# lesion-breakout.net
KiCad netlist of a schematic drawn in EAGLE
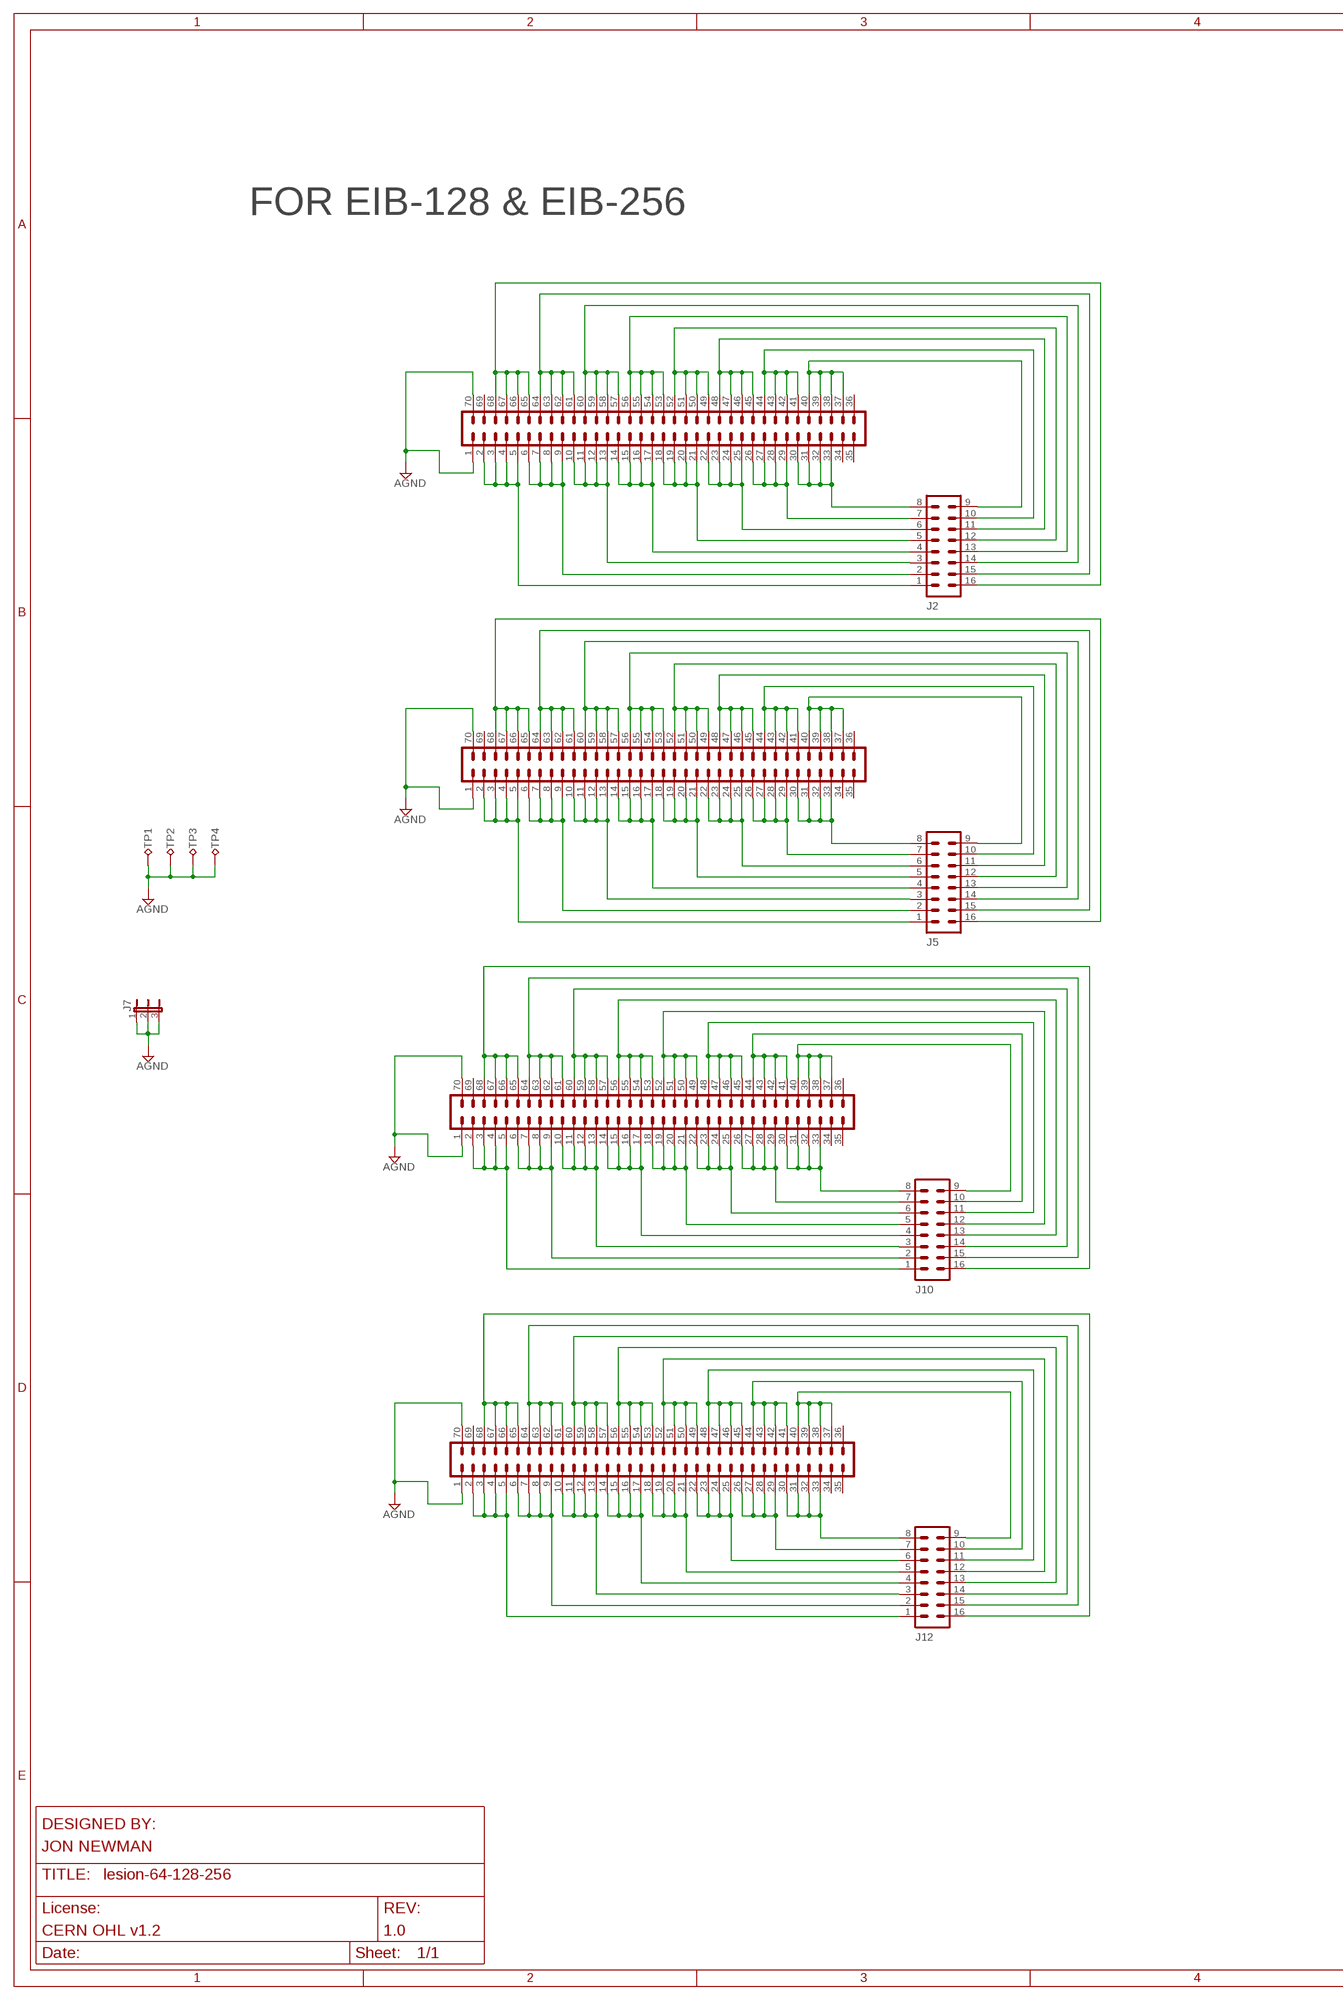
[diagram p0: schematic, sheet 1, part 1 of 3]
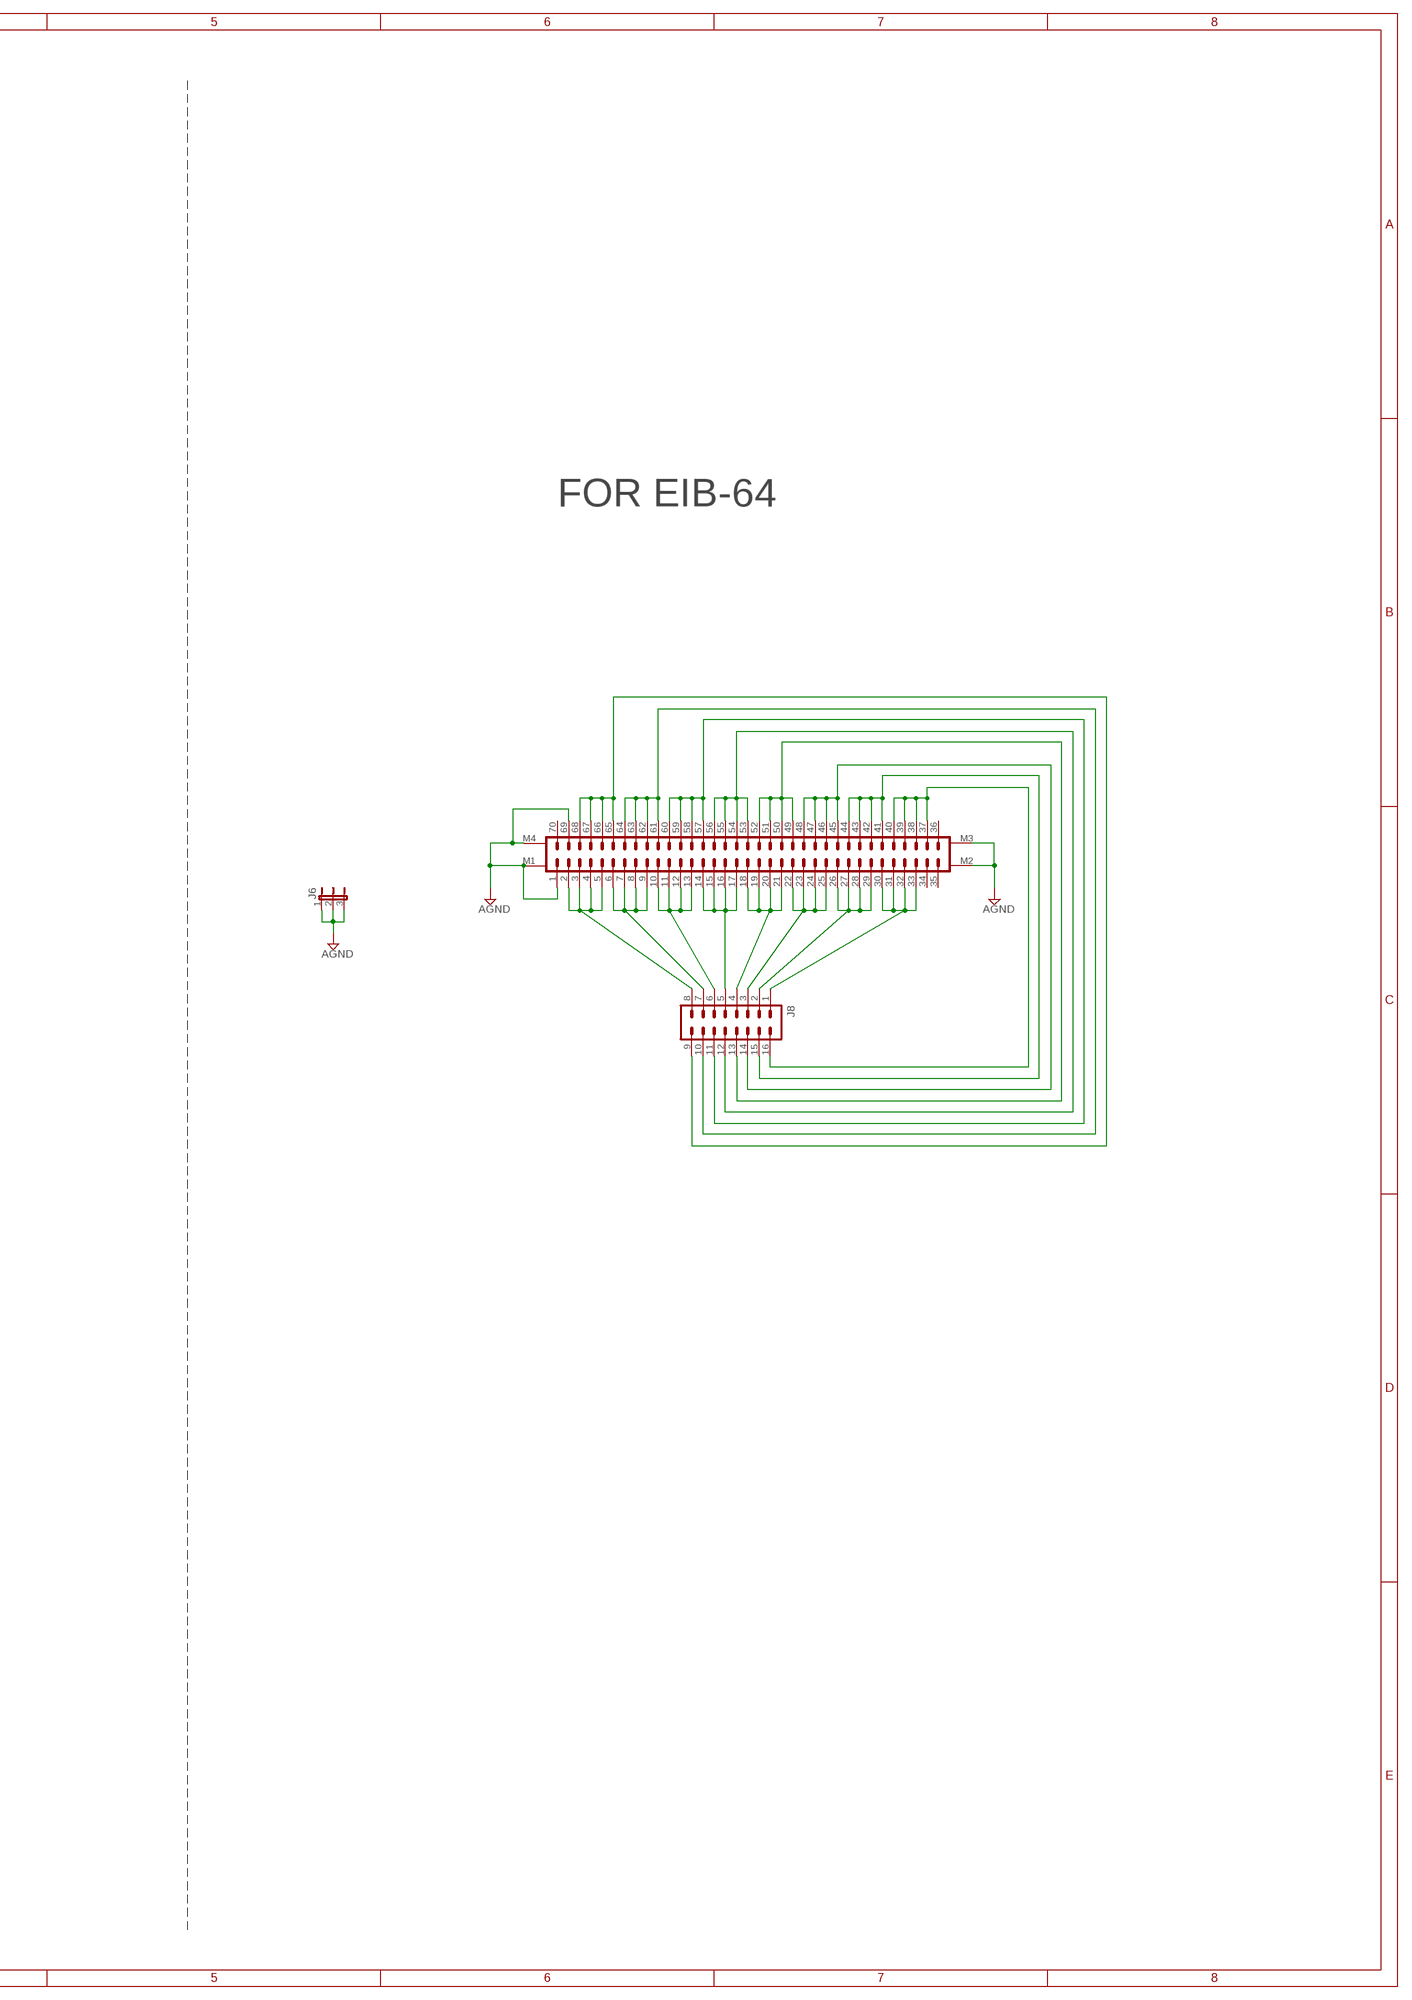
[diagram p1: schematic, sheet 1, part 2 of 3]
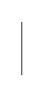
[diagram p2: schematic, sheet 1, part 3 of 3]

(export (version "E")
  (design (tool "Eeschema 10.0.6"))
  (components
    (comp (ref "J1")
      (value "DF40C(2.0)-70DS-0.4V(51)")
      (footprint "eagle-import:DF40-70REC")
      (libsource (lib "eagle-import") (part "PINHD-2X35_DF40REC"))
    )
    (comp (ref "J2")
      (value "PINHD-2X8_SMD_0.5\"")
      (footprint "eagle-import:JP2X8_SMD_0.5_")
      (libsource (lib "eagle-import") (part "PINHD-2X8_SMD_0.5{dblquote}"))
    )
    (comp (ref "J3")
      (value "DF40C(2.0)-70DS-0.4V(51)")
      (footprint "eagle-import:DF40-70REC")
      (libsource (lib "eagle-import") (part "PINHD-2X35_DF40REC"))
    )
    (comp (ref "J4")
      (value "DF40C-70DP-0.4V(51)")
      (footprint "eagle-import:DF40-70HEAD-LESS-SILK")
      (libsource (lib "eagle-import") (part "PINHD-2X35+4DF40-70HEAD-LESS-SILK"))
    )
    (comp (ref "J5")
      (value "PINHD-2X8_SMD_0.5\"")
      (footprint "eagle-import:JP2X8_SMD_0.5_")
      (libsource (lib "eagle-import") (part "PINHD-2X8_SMD_0.5{dblquote}"))
    )
    (comp (ref "J6")
      (value "JP3E_SMD-0.05")
      (footprint "eagle-import:JP3_SMD-0.05")
      (libsource (lib "eagle-import") (part "JP3E_SMD-0.05"))
    )
    (comp (ref "J7")
      (value "JP3E_SMD-0.05")
      (footprint "eagle-import:JP3_SMD-0.05")
      (libsource (lib "eagle-import") (part "JP3E_SMD-0.05"))
    )
    (comp (ref "J8")
      (value "PINHD-2X8_SMD_0.5\"")
      (footprint "eagle-import:JP2X8_SMD_0.5_")
      (libsource (lib "eagle-import") (part "PINHD-2X8_SMD_0.5{dblquote}"))
    )
    (comp (ref "J9")
      (value "DF40C(2.0)-70DS-0.4V(51)")
      (footprint "eagle-import:DF40-70REC")
      (libsource (lib "eagle-import") (part "PINHD-2X35_DF40REC"))
    )
    (comp (ref "J10")
      (value "PINHD-2X8_SMD_0.5\"")
      (footprint "eagle-import:JP2X8_SMD_0.5_")
      (libsource (lib "eagle-import") (part "PINHD-2X8_SMD_0.5{dblquote}"))
    )
    (comp (ref "J11")
      (value "DF40C(2.0)-70DS-0.4V(51)")
      (footprint "eagle-import:DF40-70REC")
      (libsource (lib "eagle-import") (part "PINHD-2X35_DF40REC"))
    )
    (comp (ref "J12")
      (value "PINHD-2X8_SMD_0.5\"")
      (footprint "eagle-import:JP2X8_SMD_0.5_")
      (libsource (lib "eagle-import") (part "PINHD-2X8_SMD_0.5{dblquote}"))
    )
    (comp (ref "TP1")
      (value "TP_1MM")
      (footprint "eagle-import:TESTPOINT_1MM")
      (libsource (lib "eagle-import") (part "TP_1MM"))
    )
    (comp (ref "TP2")
      (value "TP_1MM")
      (footprint "eagle-import:TESTPOINT_1MM")
      (libsource (lib "eagle-import") (part "TP_1MM"))
    )
    (comp (ref "TP3")
      (value "TP_1MM")
      (footprint "eagle-import:TESTPOINT_1MM")
      (libsource (lib "eagle-import") (part "TP_1MM"))
    )
    (comp (ref "TP4")
      (value "TP_1MM")
      (footprint "eagle-import:TESTPOINT_1MM")
      (libsource (lib "eagle-import") (part "TP_1MM"))
    )
  )
  (nets
    (net (code "1") (name "AGND") (class "Default")
      (node (ref "J1") (pin "1") (pinfunction "1_1") (pintype "bidirectional"))
      (node (ref "J1") (pin "70") (pinfunction "70_70") (pintype "bidirectional"))
      (node (ref "J11") (pin "1") (pinfunction "1_1") (pintype "bidirectional"))
      (node (ref "J11") (pin "70") (pinfunction "70_70") (pintype "bidirectional"))
      (node (ref "J3") (pin "1") (pinfunction "1_1") (pintype "bidirectional"))
      (node (ref "J3") (pin "70") (pinfunction "70_70") (pintype "bidirectional"))
      (node (ref "J4") (pin "1") (pinfunction "1_1") (pintype "bidirectional"))
      (node (ref "J4") (pin "69") (pinfunction "69_69") (pintype "bidirectional"))
      (node (ref "J4") (pin "M1") (pinfunction "M1_M1") (pintype "bidirectional"))
      (node (ref "J4") (pin "M2") (pinfunction "M2_M2") (pintype "bidirectional"))
      (node (ref "J4") (pin "M3") (pinfunction "M3_M3") (pintype "bidirectional"))
      (node (ref "J4") (pin "M4") (pinfunction "M4_M4") (pintype "bidirectional"))
      (node (ref "J6") (pin "1") (pinfunction "1_1") (pintype "passive"))
      (node (ref "J6") (pin "2") (pinfunction "2_2") (pintype "passive"))
      (node (ref "J6") (pin "3") (pinfunction "3_3") (pintype "passive"))
      (node (ref "J7") (pin "1") (pinfunction "1_1") (pintype "passive"))
      (node (ref "J7") (pin "2") (pinfunction "2_2") (pintype "passive"))
      (node (ref "J7") (pin "3") (pinfunction "3_3") (pintype "passive"))
      (node (ref "J9") (pin "1") (pinfunction "1_1") (pintype "bidirectional"))
      (node (ref "J9") (pin "70") (pinfunction "70_70") (pintype "bidirectional"))
      (node (ref "TP1") (pin "1") (pinfunction "TP_1") (pintype "bidirectional"))
      (node (ref "TP2") (pin "1") (pinfunction "TP_1") (pintype "bidirectional"))
      (node (ref "TP3") (pin "1") (pinfunction "TP_1") (pintype "bidirectional"))
      (node (ref "TP4") (pin "1") (pinfunction "TP_1") (pintype "bidirectional"))
    )
    (net (code "2") (name "Net-(J1-Pad2)") (class "Default")
      (node (ref "J1") (pin "2") (pinfunction "2_2") (pintype "bidirectional"))
      (node (ref "J1") (pin "3") (pinfunction "3_3") (pintype "bidirectional"))
      (node (ref "J1") (pin "4") (pinfunction "4_4") (pintype "bidirectional"))
      (node (ref "J1") (pin "5") (pinfunction "5_5") (pintype "bidirectional"))
      (node (ref "J2") (pin "1") (pinfunction "1_1") (pintype "passive"))
    )
    (net (code "3") (name "Net-(J2-2)") (class "Default")
      (node (ref "J1") (pin "65") (pinfunction "65_65") (pintype "bidirectional"))
      (node (ref "J1") (pin "66") (pinfunction "66_66") (pintype "bidirectional"))
      (node (ref "J1") (pin "67") (pinfunction "67_67") (pintype "bidirectional"))
      (node (ref "J1") (pin "68") (pinfunction "68_68") (pintype "bidirectional"))
      (node (ref "J2") (pin "16") (pinfunction "2_16") (pintype "passive"))
    )
    (net (code "4") (name "Net-(J2-3)") (class "Default")
      (node (ref "J1") (pin "6") (pinfunction "6_6") (pintype "bidirectional"))
      (node (ref "J1") (pin "7") (pinfunction "7_7") (pintype "bidirectional"))
      (node (ref "J1") (pin "8") (pinfunction "8_8") (pintype "bidirectional"))
      (node (ref "J1") (pin "9") (pinfunction "9_9") (pintype "bidirectional"))
      (node (ref "J2") (pin "2") (pinfunction "3_2") (pintype "passive"))
    )
    (net (code "5") (name "Net-(J2-4)") (class "Default")
      (node (ref "J1") (pin "61") (pinfunction "61_61") (pintype "bidirectional"))
      (node (ref "J1") (pin "62") (pinfunction "62_62") (pintype "bidirectional"))
      (node (ref "J1") (pin "63") (pinfunction "63_63") (pintype "bidirectional"))
      (node (ref "J1") (pin "64") (pinfunction "64_64") (pintype "bidirectional"))
      (node (ref "J2") (pin "15") (pinfunction "4_15") (pintype "passive"))
    )
    (net (code "6") (name "Net-(J2-5)") (class "Default")
      (node (ref "J1") (pin "10") (pinfunction "10_10") (pintype "bidirectional"))
      (node (ref "J1") (pin "11") (pinfunction "11_11") (pintype "bidirectional"))
      (node (ref "J1") (pin "12") (pinfunction "12_12") (pintype "bidirectional"))
      (node (ref "J1") (pin "13") (pinfunction "13_13") (pintype "bidirectional"))
      (node (ref "J2") (pin "3") (pinfunction "5_3") (pintype "passive"))
    )
    (net (code "7") (name "Net-(J2-6)") (class "Default")
      (node (ref "J1") (pin "57") (pinfunction "57_57") (pintype "bidirectional"))
      (node (ref "J1") (pin "58") (pinfunction "58_58") (pintype "bidirectional"))
      (node (ref "J1") (pin "59") (pinfunction "59_59") (pintype "bidirectional"))
      (node (ref "J1") (pin "60") (pinfunction "60_60") (pintype "bidirectional"))
      (node (ref "J2") (pin "14") (pinfunction "6_14") (pintype "passive"))
    )
    (net (code "8") (name "Net-(J2-7)") (class "Default")
      (node (ref "J1") (pin "14") (pinfunction "14_14") (pintype "bidirectional"))
      (node (ref "J1") (pin "15") (pinfunction "15_15") (pintype "bidirectional"))
      (node (ref "J1") (pin "16") (pinfunction "16_16") (pintype "bidirectional"))
      (node (ref "J1") (pin "17") (pinfunction "17_17") (pintype "bidirectional"))
      (node (ref "J2") (pin "4") (pinfunction "7_4") (pintype "passive"))
    )
    (net (code "9") (name "Net-(J2-8)") (class "Default")
      (node (ref "J1") (pin "53") (pinfunction "53_53") (pintype "bidirectional"))
      (node (ref "J1") (pin "54") (pinfunction "54_54") (pintype "bidirectional"))
      (node (ref "J1") (pin "55") (pinfunction "55_55") (pintype "bidirectional"))
      (node (ref "J1") (pin "56") (pinfunction "56_56") (pintype "bidirectional"))
      (node (ref "J2") (pin "13") (pinfunction "8_13") (pintype "passive"))
    )
    (net (code "10") (name "Net-(J2-9)") (class "Default")
      (node (ref "J1") (pin "18") (pinfunction "18_18") (pintype "bidirectional"))
      (node (ref "J1") (pin "19") (pinfunction "19_19") (pintype "bidirectional"))
      (node (ref "J1") (pin "20") (pinfunction "20_20") (pintype "bidirectional"))
      (node (ref "J1") (pin "21") (pinfunction "21_21") (pintype "bidirectional"))
      (node (ref "J2") (pin "5") (pinfunction "9_5") (pintype "passive"))
    )
    (net (code "11") (name "Net-(J2-10)") (class "Default")
      (node (ref "J1") (pin "49") (pinfunction "49_49") (pintype "bidirectional"))
      (node (ref "J1") (pin "50") (pinfunction "50_50") (pintype "bidirectional"))
      (node (ref "J1") (pin "51") (pinfunction "51_51") (pintype "bidirectional"))
      (node (ref "J1") (pin "52") (pinfunction "52_52") (pintype "bidirectional"))
      (node (ref "J2") (pin "12") (pinfunction "10_12") (pintype "passive"))
    )
    (net (code "12") (name "Net-(J2-11)") (class "Default")
      (node (ref "J1") (pin "22") (pinfunction "22_22") (pintype "bidirectional"))
      (node (ref "J1") (pin "23") (pinfunction "23_23") (pintype "bidirectional"))
      (node (ref "J1") (pin "24") (pinfunction "24_24") (pintype "bidirectional"))
      (node (ref "J1") (pin "25") (pinfunction "25_25") (pintype "bidirectional"))
      (node (ref "J2") (pin "6") (pinfunction "11_6") (pintype "passive"))
    )
    (net (code "13") (name "Net-(J2-12)") (class "Default")
      (node (ref "J1") (pin "45") (pinfunction "45_45") (pintype "bidirectional"))
      (node (ref "J1") (pin "46") (pinfunction "46_46") (pintype "bidirectional"))
      (node (ref "J1") (pin "47") (pinfunction "47_47") (pintype "bidirectional"))
      (node (ref "J1") (pin "48") (pinfunction "48_48") (pintype "bidirectional"))
      (node (ref "J2") (pin "11") (pinfunction "12_11") (pintype "passive"))
    )
    (net (code "14") (name "Net-(J2-13)") (class "Default")
      (node (ref "J1") (pin "26") (pinfunction "26_26") (pintype "bidirectional"))
      (node (ref "J1") (pin "27") (pinfunction "27_27") (pintype "bidirectional"))
      (node (ref "J1") (pin "28") (pinfunction "28_28") (pintype "bidirectional"))
      (node (ref "J1") (pin "29") (pinfunction "29_29") (pintype "bidirectional"))
      (node (ref "J2") (pin "7") (pinfunction "13_7") (pintype "passive"))
    )
    (net (code "15") (name "Net-(J2-14)") (class "Default")
      (node (ref "J1") (pin "41") (pinfunction "41_41") (pintype "bidirectional"))
      (node (ref "J1") (pin "42") (pinfunction "42_42") (pintype "bidirectional"))
      (node (ref "J1") (pin "43") (pinfunction "43_43") (pintype "bidirectional"))
      (node (ref "J1") (pin "44") (pinfunction "44_44") (pintype "bidirectional"))
      (node (ref "J2") (pin "10") (pinfunction "14_10") (pintype "passive"))
    )
    (net (code "16") (name "Net-(J2-15)") (class "Default")
      (node (ref "J1") (pin "30") (pinfunction "30_30") (pintype "bidirectional"))
      (node (ref "J1") (pin "31") (pinfunction "31_31") (pintype "bidirectional"))
      (node (ref "J1") (pin "32") (pinfunction "32_32") (pintype "bidirectional"))
      (node (ref "J1") (pin "33") (pinfunction "33_33") (pintype "bidirectional"))
      (node (ref "J2") (pin "8") (pinfunction "15_8") (pintype "passive"))
    )
    (net (code "17") (name "Net-(J2-16)") (class "Default")
      (node (ref "J1") (pin "37") (pinfunction "37_37") (pintype "bidirectional"))
      (node (ref "J1") (pin "38") (pinfunction "38_38") (pintype "bidirectional"))
      (node (ref "J1") (pin "39") (pinfunction "39_39") (pintype "bidirectional"))
      (node (ref "J1") (pin "40") (pinfunction "40_40") (pintype "bidirectional"))
      (node (ref "J2") (pin "9") (pinfunction "16_9") (pintype "passive"))
    )
    (net (code "18") (name "Net-(J3-Pad2)") (class "Default")
      (node (ref "J3") (pin "2") (pinfunction "2_2") (pintype "bidirectional"))
      (node (ref "J3") (pin "3") (pinfunction "3_3") (pintype "bidirectional"))
      (node (ref "J3") (pin "4") (pinfunction "4_4") (pintype "bidirectional"))
      (node (ref "J3") (pin "5") (pinfunction "5_5") (pintype "bidirectional"))
      (node (ref "J5") (pin "1") (pinfunction "1_1") (pintype "passive"))
    )
    (net (code "19") (name "Net-(J4-Pad30)") (class "Default")
      (node (ref "J4") (pin "30") (pinfunction "30_30") (pintype "bidirectional"))
      (node (ref "J4") (pin "31") (pinfunction "31_31") (pintype "bidirectional"))
      (node (ref "J4") (pin "32") (pinfunction "32_32") (pintype "bidirectional"))
      (node (ref "J4") (pin "33") (pinfunction "33_33") (pintype "bidirectional"))
      (node (ref "J8") (pin "1") (pinfunction "1_1") (pintype "passive"))
    )
    (net (code "20") (name "Net-(J5-2)") (class "Default")
      (node (ref "J3") (pin "65") (pinfunction "65_65") (pintype "bidirectional"))
      (node (ref "J3") (pin "66") (pinfunction "66_66") (pintype "bidirectional"))
      (node (ref "J3") (pin "67") (pinfunction "67_67") (pintype "bidirectional"))
      (node (ref "J3") (pin "68") (pinfunction "68_68") (pintype "bidirectional"))
      (node (ref "J5") (pin "16") (pinfunction "2_16") (pintype "passive"))
    )
    (net (code "21") (name "Net-(J5-3)") (class "Default")
      (node (ref "J3") (pin "6") (pinfunction "6_6") (pintype "bidirectional"))
      (node (ref "J3") (pin "7") (pinfunction "7_7") (pintype "bidirectional"))
      (node (ref "J3") (pin "8") (pinfunction "8_8") (pintype "bidirectional"))
      (node (ref "J3") (pin "9") (pinfunction "9_9") (pintype "bidirectional"))
      (node (ref "J5") (pin "2") (pinfunction "3_2") (pintype "passive"))
    )
    (net (code "22") (name "Net-(J5-4)") (class "Default")
      (node (ref "J3") (pin "61") (pinfunction "61_61") (pintype "bidirectional"))
      (node (ref "J3") (pin "62") (pinfunction "62_62") (pintype "bidirectional"))
      (node (ref "J3") (pin "63") (pinfunction "63_63") (pintype "bidirectional"))
      (node (ref "J3") (pin "64") (pinfunction "64_64") (pintype "bidirectional"))
      (node (ref "J5") (pin "15") (pinfunction "4_15") (pintype "passive"))
    )
    (net (code "23") (name "Net-(J5-5)") (class "Default")
      (node (ref "J3") (pin "10") (pinfunction "10_10") (pintype "bidirectional"))
      (node (ref "J3") (pin "11") (pinfunction "11_11") (pintype "bidirectional"))
      (node (ref "J3") (pin "12") (pinfunction "12_12") (pintype "bidirectional"))
      (node (ref "J3") (pin "13") (pinfunction "13_13") (pintype "bidirectional"))
      (node (ref "J5") (pin "3") (pinfunction "5_3") (pintype "passive"))
    )
    (net (code "24") (name "Net-(J5-6)") (class "Default")
      (node (ref "J3") (pin "57") (pinfunction "57_57") (pintype "bidirectional"))
      (node (ref "J3") (pin "58") (pinfunction "58_58") (pintype "bidirectional"))
      (node (ref "J3") (pin "59") (pinfunction "59_59") (pintype "bidirectional"))
      (node (ref "J3") (pin "60") (pinfunction "60_60") (pintype "bidirectional"))
      (node (ref "J5") (pin "14") (pinfunction "6_14") (pintype "passive"))
    )
    (net (code "25") (name "Net-(J5-7)") (class "Default")
      (node (ref "J3") (pin "14") (pinfunction "14_14") (pintype "bidirectional"))
      (node (ref "J3") (pin "15") (pinfunction "15_15") (pintype "bidirectional"))
      (node (ref "J3") (pin "16") (pinfunction "16_16") (pintype "bidirectional"))
      (node (ref "J3") (pin "17") (pinfunction "17_17") (pintype "bidirectional"))
      (node (ref "J5") (pin "4") (pinfunction "7_4") (pintype "passive"))
    )
    (net (code "26") (name "Net-(J5-8)") (class "Default")
      (node (ref "J3") (pin "53") (pinfunction "53_53") (pintype "bidirectional"))
      (node (ref "J3") (pin "54") (pinfunction "54_54") (pintype "bidirectional"))
      (node (ref "J3") (pin "55") (pinfunction "55_55") (pintype "bidirectional"))
      (node (ref "J3") (pin "56") (pinfunction "56_56") (pintype "bidirectional"))
      (node (ref "J5") (pin "13") (pinfunction "8_13") (pintype "passive"))
    )
    (net (code "27") (name "Net-(J5-9)") (class "Default")
      (node (ref "J3") (pin "18") (pinfunction "18_18") (pintype "bidirectional"))
      (node (ref "J3") (pin "19") (pinfunction "19_19") (pintype "bidirectional"))
      (node (ref "J3") (pin "20") (pinfunction "20_20") (pintype "bidirectional"))
      (node (ref "J3") (pin "21") (pinfunction "21_21") (pintype "bidirectional"))
      (node (ref "J5") (pin "5") (pinfunction "9_5") (pintype "passive"))
    )
    (net (code "28") (name "Net-(J5-10)") (class "Default")
      (node (ref "J3") (pin "49") (pinfunction "49_49") (pintype "bidirectional"))
      (node (ref "J3") (pin "50") (pinfunction "50_50") (pintype "bidirectional"))
      (node (ref "J3") (pin "51") (pinfunction "51_51") (pintype "bidirectional"))
      (node (ref "J3") (pin "52") (pinfunction "52_52") (pintype "bidirectional"))
      (node (ref "J5") (pin "12") (pinfunction "10_12") (pintype "passive"))
    )
    (net (code "29") (name "Net-(J5-11)") (class "Default")
      (node (ref "J3") (pin "22") (pinfunction "22_22") (pintype "bidirectional"))
      (node (ref "J3") (pin "23") (pinfunction "23_23") (pintype "bidirectional"))
      (node (ref "J3") (pin "24") (pinfunction "24_24") (pintype "bidirectional"))
      (node (ref "J3") (pin "25") (pinfunction "25_25") (pintype "bidirectional"))
      (node (ref "J5") (pin "6") (pinfunction "11_6") (pintype "passive"))
    )
    (net (code "30") (name "Net-(J5-12)") (class "Default")
      (node (ref "J3") (pin "45") (pinfunction "45_45") (pintype "bidirectional"))
      (node (ref "J3") (pin "46") (pinfunction "46_46") (pintype "bidirectional"))
      (node (ref "J3") (pin "47") (pinfunction "47_47") (pintype "bidirectional"))
      (node (ref "J3") (pin "48") (pinfunction "48_48") (pintype "bidirectional"))
      (node (ref "J5") (pin "11") (pinfunction "12_11") (pintype "passive"))
    )
    (net (code "31") (name "Net-(J5-13)") (class "Default")
      (node (ref "J3") (pin "26") (pinfunction "26_26") (pintype "bidirectional"))
      (node (ref "J3") (pin "27") (pinfunction "27_27") (pintype "bidirectional"))
      (node (ref "J3") (pin "28") (pinfunction "28_28") (pintype "bidirectional"))
      (node (ref "J3") (pin "29") (pinfunction "29_29") (pintype "bidirectional"))
      (node (ref "J5") (pin "7") (pinfunction "13_7") (pintype "passive"))
    )
    (net (code "32") (name "Net-(J5-14)") (class "Default")
      (node (ref "J3") (pin "41") (pinfunction "41_41") (pintype "bidirectional"))
      (node (ref "J3") (pin "42") (pinfunction "42_42") (pintype "bidirectional"))
      (node (ref "J3") (pin "43") (pinfunction "43_43") (pintype "bidirectional"))
      (node (ref "J3") (pin "44") (pinfunction "44_44") (pintype "bidirectional"))
      (node (ref "J5") (pin "10") (pinfunction "14_10") (pintype "passive"))
    )
    (net (code "33") (name "Net-(J5-15)") (class "Default")
      (node (ref "J3") (pin "30") (pinfunction "30_30") (pintype "bidirectional"))
      (node (ref "J3") (pin "31") (pinfunction "31_31") (pintype "bidirectional"))
      (node (ref "J3") (pin "32") (pinfunction "32_32") (pintype "bidirectional"))
      (node (ref "J3") (pin "33") (pinfunction "33_33") (pintype "bidirectional"))
      (node (ref "J5") (pin "8") (pinfunction "15_8") (pintype "passive"))
    )
    (net (code "34") (name "Net-(J5-16)") (class "Default")
      (node (ref "J3") (pin "37") (pinfunction "37_37") (pintype "bidirectional"))
      (node (ref "J3") (pin "38") (pinfunction "38_38") (pintype "bidirectional"))
      (node (ref "J3") (pin "39") (pinfunction "39_39") (pintype "bidirectional"))
      (node (ref "J3") (pin "40") (pinfunction "40_40") (pintype "bidirectional"))
      (node (ref "J5") (pin "9") (pinfunction "16_9") (pintype "passive"))
    )
    (net (code "35") (name "Net-(J8-2)") (class "Default")
      (node (ref "J4") (pin "37") (pinfunction "37_37") (pintype "bidirectional"))
      (node (ref "J4") (pin "38") (pinfunction "38_38") (pintype "bidirectional"))
      (node (ref "J4") (pin "39") (pinfunction "39_39") (pintype "bidirectional"))
      (node (ref "J4") (pin "40") (pinfunction "40_40") (pintype "bidirectional"))
      (node (ref "J8") (pin "16") (pinfunction "2_16") (pintype "passive"))
    )
    (net (code "36") (name "Net-(J8-3)") (class "Default")
      (node (ref "J4") (pin "26") (pinfunction "26_26") (pintype "bidirectional"))
      (node (ref "J4") (pin "27") (pinfunction "27_27") (pintype "bidirectional"))
      (node (ref "J4") (pin "28") (pinfunction "28_28") (pintype "bidirectional"))
      (node (ref "J4") (pin "29") (pinfunction "29_29") (pintype "bidirectional"))
      (node (ref "J8") (pin "2") (pinfunction "3_2") (pintype "passive"))
    )
    (net (code "37") (name "Net-(J8-4)") (class "Default")
      (node (ref "J4") (pin "41") (pinfunction "41_41") (pintype "bidirectional"))
      (node (ref "J4") (pin "42") (pinfunction "42_42") (pintype "bidirectional"))
      (node (ref "J4") (pin "43") (pinfunction "43_43") (pintype "bidirectional"))
      (node (ref "J4") (pin "44") (pinfunction "44_44") (pintype "bidirectional"))
      (node (ref "J8") (pin "15") (pinfunction "4_15") (pintype "passive"))
    )
    (net (code "38") (name "Net-(J8-5)") (class "Default")
      (node (ref "J4") (pin "22") (pinfunction "22_22") (pintype "bidirectional"))
      (node (ref "J4") (pin "23") (pinfunction "23_23") (pintype "bidirectional"))
      (node (ref "J4") (pin "24") (pinfunction "24_24") (pintype "bidirectional"))
      (node (ref "J4") (pin "25") (pinfunction "25_25") (pintype "bidirectional"))
      (node (ref "J8") (pin "3") (pinfunction "5_3") (pintype "passive"))
    )
    (net (code "39") (name "Net-(J8-6)") (class "Default")
      (node (ref "J4") (pin "45") (pinfunction "45_45") (pintype "bidirectional"))
      (node (ref "J4") (pin "46") (pinfunction "46_46") (pintype "bidirectional"))
      (node (ref "J4") (pin "47") (pinfunction "47_47") (pintype "bidirectional"))
      (node (ref "J4") (pin "48") (pinfunction "48_48") (pintype "bidirectional"))
      (node (ref "J8") (pin "14") (pinfunction "6_14") (pintype "passive"))
    )
    (net (code "40") (name "Net-(J8-7)") (class "Default")
      (node (ref "J4") (pin "18") (pinfunction "18_18") (pintype "bidirectional"))
      (node (ref "J4") (pin "19") (pinfunction "19_19") (pintype "bidirectional"))
      (node (ref "J4") (pin "20") (pinfunction "20_20") (pintype "bidirectional"))
      (node (ref "J4") (pin "21") (pinfunction "21_21") (pintype "bidirectional"))
      (node (ref "J8") (pin "4") (pinfunction "7_4") (pintype "passive"))
    )
    (net (code "41") (name "Net-(J8-8)") (class "Default")
      (node (ref "J4") (pin "49") (pinfunction "49_49") (pintype "bidirectional"))
      (node (ref "J4") (pin "50") (pinfunction "50_50") (pintype "bidirectional"))
      (node (ref "J4") (pin "51") (pinfunction "51_51") (pintype "bidirectional"))
      (node (ref "J4") (pin "52") (pinfunction "52_52") (pintype "bidirectional"))
      (node (ref "J8") (pin "13") (pinfunction "8_13") (pintype "passive"))
    )
    (net (code "42") (name "Net-(J8-9)") (class "Default")
      (node (ref "J4") (pin "14") (pinfunction "14_14") (pintype "bidirectional"))
      (node (ref "J4") (pin "15") (pinfunction "15_15") (pintype "bidirectional"))
      (node (ref "J4") (pin "16") (pinfunction "16_16") (pintype "bidirectional"))
      (node (ref "J4") (pin "17") (pinfunction "17_17") (pintype "bidirectional"))
      (node (ref "J8") (pin "5") (pinfunction "9_5") (pintype "passive"))
    )
    (net (code "43") (name "Net-(J8-10)") (class "Default")
      (node (ref "J4") (pin "53") (pinfunction "53_53") (pintype "bidirectional"))
      (node (ref "J4") (pin "54") (pinfunction "54_54") (pintype "bidirectional"))
      (node (ref "J4") (pin "55") (pinfunction "55_55") (pintype "bidirectional"))
      (node (ref "J4") (pin "56") (pinfunction "56_56") (pintype "bidirectional"))
      (node (ref "J8") (pin "12") (pinfunction "10_12") (pintype "passive"))
    )
    (net (code "44") (name "Net-(J8-11)") (class "Default")
      (node (ref "J4") (pin "10") (pinfunction "10_10") (pintype "bidirectional"))
      (node (ref "J4") (pin "11") (pinfunction "11_11") (pintype "bidirectional"))
      (node (ref "J4") (pin "12") (pinfunction "12_12") (pintype "bidirectional"))
      (node (ref "J4") (pin "13") (pinfunction "13_13") (pintype "bidirectional"))
      (node (ref "J8") (pin "6") (pinfunction "11_6") (pintype "passive"))
    )
    (net (code "45") (name "Net-(J8-12)") (class "Default")
      (node (ref "J4") (pin "57") (pinfunction "57_57") (pintype "bidirectional"))
      (node (ref "J4") (pin "58") (pinfunction "58_58") (pintype "bidirectional"))
      (node (ref "J4") (pin "59") (pinfunction "59_59") (pintype "bidirectional"))
      (node (ref "J4") (pin "60") (pinfunction "60_60") (pintype "bidirectional"))
      (node (ref "J8") (pin "11") (pinfunction "12_11") (pintype "passive"))
    )
    (net (code "46") (name "Net-(J8-13)") (class "Default")
      (node (ref "J4") (pin "6") (pinfunction "6_6") (pintype "bidirectional"))
      (node (ref "J4") (pin "7") (pinfunction "7_7") (pintype "bidirectional"))
      (node (ref "J4") (pin "8") (pinfunction "8_8") (pintype "bidirectional"))
      (node (ref "J4") (pin "9") (pinfunction "9_9") (pintype "bidirectional"))
      (node (ref "J8") (pin "7") (pinfunction "13_7") (pintype "passive"))
    )
    (net (code "47") (name "Net-(J8-14)") (class "Default")
      (node (ref "J4") (pin "61") (pinfunction "61_61") (pintype "bidirectional"))
      (node (ref "J4") (pin "62") (pinfunction "62_62") (pintype "bidirectional"))
      (node (ref "J4") (pin "63") (pinfunction "63_63") (pintype "bidirectional"))
      (node (ref "J4") (pin "64") (pinfunction "64_64") (pintype "bidirectional"))
      (node (ref "J8") (pin "10") (pinfunction "14_10") (pintype "passive"))
    )
    (net (code "48") (name "Net-(J8-15)") (class "Default")
      (node (ref "J4") (pin "2") (pinfunction "2_2") (pintype "bidirectional"))
      (node (ref "J4") (pin "3") (pinfunction "3_3") (pintype "bidirectional"))
      (node (ref "J4") (pin "4") (pinfunction "4_4") (pintype "bidirectional"))
      (node (ref "J4") (pin "5") (pinfunction "5_5") (pintype "bidirectional"))
      (node (ref "J8") (pin "8") (pinfunction "15_8") (pintype "passive"))
    )
    (net (code "49") (name "Net-(J8-16)") (class "Default")
      (node (ref "J4") (pin "65") (pinfunction "65_65") (pintype "bidirectional"))
      (node (ref "J4") (pin "66") (pinfunction "66_66") (pintype "bidirectional"))
      (node (ref "J4") (pin "67") (pinfunction "67_67") (pintype "bidirectional"))
      (node (ref "J4") (pin "68") (pinfunction "68_68") (pintype "bidirectional"))
      (node (ref "J8") (pin "9") (pinfunction "16_9") (pintype "passive"))
    )
    (net (code "50") (name "Net-(J10-2)") (class "Default")
      (node (ref "J10") (pin "16") (pinfunction "2_16") (pintype "passive"))
      (node (ref "J9") (pin "65") (pinfunction "65_65") (pintype "bidirectional"))
      (node (ref "J9") (pin "66") (pinfunction "66_66") (pintype "bidirectional"))
      (node (ref "J9") (pin "67") (pinfunction "67_67") (pintype "bidirectional"))
      (node (ref "J9") (pin "68") (pinfunction "68_68") (pintype "bidirectional"))
    )
    (net (code "51") (name "Net-(J10-3)") (class "Default")
      (node (ref "J10") (pin "2") (pinfunction "3_2") (pintype "passive"))
      (node (ref "J9") (pin "6") (pinfunction "6_6") (pintype "bidirectional"))
      (node (ref "J9") (pin "7") (pinfunction "7_7") (pintype "bidirectional"))
      (node (ref "J9") (pin "8") (pinfunction "8_8") (pintype "bidirectional"))
      (node (ref "J9") (pin "9") (pinfunction "9_9") (pintype "bidirectional"))
    )
    (net (code "52") (name "Net-(J10-4)") (class "Default")
      (node (ref "J10") (pin "15") (pinfunction "4_15") (pintype "passive"))
      (node (ref "J9") (pin "61") (pinfunction "61_61") (pintype "bidirectional"))
      (node (ref "J9") (pin "62") (pinfunction "62_62") (pintype "bidirectional"))
      (node (ref "J9") (pin "63") (pinfunction "63_63") (pintype "bidirectional"))
      (node (ref "J9") (pin "64") (pinfunction "64_64") (pintype "bidirectional"))
    )
    (net (code "53") (name "Net-(J10-5)") (class "Default")
      (node (ref "J10") (pin "3") (pinfunction "5_3") (pintype "passive"))
      (node (ref "J9") (pin "10") (pinfunction "10_10") (pintype "bidirectional"))
      (node (ref "J9") (pin "11") (pinfunction "11_11") (pintype "bidirectional"))
      (node (ref "J9") (pin "12") (pinfunction "12_12") (pintype "bidirectional"))
      (node (ref "J9") (pin "13") (pinfunction "13_13") (pintype "bidirectional"))
    )
    (net (code "54") (name "Net-(J10-6)") (class "Default")
      (node (ref "J10") (pin "14") (pinfunction "6_14") (pintype "passive"))
      (node (ref "J9") (pin "57") (pinfunction "57_57") (pintype "bidirectional"))
      (node (ref "J9") (pin "58") (pinfunction "58_58") (pintype "bidirectional"))
      (node (ref "J9") (pin "59") (pinfunction "59_59") (pintype "bidirectional"))
      (node (ref "J9") (pin "60") (pinfunction "60_60") (pintype "bidirectional"))
    )
    (net (code "55") (name "Net-(J10-7)") (class "Default")
      (node (ref "J10") (pin "4") (pinfunction "7_4") (pintype "passive"))
      (node (ref "J9") (pin "14") (pinfunction "14_14") (pintype "bidirectional"))
      (node (ref "J9") (pin "15") (pinfunction "15_15") (pintype "bidirectional"))
      (node (ref "J9") (pin "16") (pinfunction "16_16") (pintype "bidirectional"))
      (node (ref "J9") (pin "17") (pinfunction "17_17") (pintype "bidirectional"))
    )
    (net (code "56") (name "Net-(J10-8)") (class "Default")
      (node (ref "J10") (pin "13") (pinfunction "8_13") (pintype "passive"))
      (node (ref "J9") (pin "53") (pinfunction "53_53") (pintype "bidirectional"))
      (node (ref "J9") (pin "54") (pinfunction "54_54") (pintype "bidirectional"))
      (node (ref "J9") (pin "55") (pinfunction "55_55") (pintype "bidirectional"))
      (node (ref "J9") (pin "56") (pinfunction "56_56") (pintype "bidirectional"))
    )
    (net (code "57") (name "Net-(J10-9)") (class "Default")
      (node (ref "J10") (pin "5") (pinfunction "9_5") (pintype "passive"))
      (node (ref "J9") (pin "18") (pinfunction "18_18") (pintype "bidirectional"))
      (node (ref "J9") (pin "19") (pinfunction "19_19") (pintype "bidirectional"))
      (node (ref "J9") (pin "20") (pinfunction "20_20") (pintype "bidirectional"))
      (node (ref "J9") (pin "21") (pinfunction "21_21") (pintype "bidirectional"))
    )
    (net (code "58") (name "Net-(J10-10)") (class "Default")
      (node (ref "J10") (pin "12") (pinfunction "10_12") (pintype "passive"))
      (node (ref "J9") (pin "49") (pinfunction "49_49") (pintype "bidirectional"))
      (node (ref "J9") (pin "50") (pinfunction "50_50") (pintype "bidirectional"))
      (node (ref "J9") (pin "51") (pinfunction "51_51") (pintype "bidirectional"))
      (node (ref "J9") (pin "52") (pinfunction "52_52") (pintype "bidirectional"))
    )
    (net (code "59") (name "Net-(J10-11)") (class "Default")
      (node (ref "J10") (pin "6") (pinfunction "11_6") (pintype "passive"))
      (node (ref "J9") (pin "22") (pinfunction "22_22") (pintype "bidirectional"))
      (node (ref "J9") (pin "23") (pinfunction "23_23") (pintype "bidirectional"))
      (node (ref "J9") (pin "24") (pinfunction "24_24") (pintype "bidirectional"))
      (node (ref "J9") (pin "25") (pinfunction "25_25") (pintype "bidirectional"))
    )
    (net (code "60") (name "Net-(J10-12)") (class "Default")
      (node (ref "J10") (pin "11") (pinfunction "12_11") (pintype "passive"))
      (node (ref "J9") (pin "45") (pinfunction "45_45") (pintype "bidirectional"))
      (node (ref "J9") (pin "46") (pinfunction "46_46") (pintype "bidirectional"))
      (node (ref "J9") (pin "47") (pinfunction "47_47") (pintype "bidirectional"))
      (node (ref "J9") (pin "48") (pinfunction "48_48") (pintype "bidirectional"))
    )
    (net (code "61") (name "Net-(J10-13)") (class "Default")
      (node (ref "J10") (pin "7") (pinfunction "13_7") (pintype "passive"))
      (node (ref "J9") (pin "26") (pinfunction "26_26") (pintype "bidirectional"))
      (node (ref "J9") (pin "27") (pinfunction "27_27") (pintype "bidirectional"))
      (node (ref "J9") (pin "28") (pinfunction "28_28") (pintype "bidirectional"))
      (node (ref "J9") (pin "29") (pinfunction "29_29") (pintype "bidirectional"))
    )
    (net (code "62") (name "Net-(J10-14)") (class "Default")
      (node (ref "J10") (pin "10") (pinfunction "14_10") (pintype "passive"))
      (node (ref "J9") (pin "41") (pinfunction "41_41") (pintype "bidirectional"))
      (node (ref "J9") (pin "42") (pinfunction "42_42") (pintype "bidirectional"))
      (node (ref "J9") (pin "43") (pinfunction "43_43") (pintype "bidirectional"))
      (node (ref "J9") (pin "44") (pinfunction "44_44") (pintype "bidirectional"))
    )
    (net (code "63") (name "Net-(J10-15)") (class "Default")
      (node (ref "J10") (pin "8") (pinfunction "15_8") (pintype "passive"))
      (node (ref "J9") (pin "30") (pinfunction "30_30") (pintype "bidirectional"))
      (node (ref "J9") (pin "31") (pinfunction "31_31") (pintype "bidirectional"))
      (node (ref "J9") (pin "32") (pinfunction "32_32") (pintype "bidirectional"))
      (node (ref "J9") (pin "33") (pinfunction "33_33") (pintype "bidirectional"))
    )
    (net (code "64") (name "Net-(J10-16)") (class "Default")
      (node (ref "J10") (pin "9") (pinfunction "16_9") (pintype "passive"))
      (node (ref "J9") (pin "37") (pinfunction "37_37") (pintype "bidirectional"))
      (node (ref "J9") (pin "38") (pinfunction "38_38") (pintype "bidirectional"))
      (node (ref "J9") (pin "39") (pinfunction "39_39") (pintype "bidirectional"))
      (node (ref "J9") (pin "40") (pinfunction "40_40") (pintype "bidirectional"))
    )
    (net (code "65") (name "Net-(J10-Pad1)") (class "Default")
      (node (ref "J10") (pin "1") (pinfunction "1_1") (pintype "passive"))
      (node (ref "J9") (pin "2") (pinfunction "2_2") (pintype "bidirectional"))
      (node (ref "J9") (pin "3") (pinfunction "3_3") (pintype "bidirectional"))
      (node (ref "J9") (pin "4") (pinfunction "4_4") (pintype "bidirectional"))
      (node (ref "J9") (pin "5") (pinfunction "5_5") (pintype "bidirectional"))
    )
    (net (code "66") (name "Net-(J11-Pad2)") (class "Default")
      (node (ref "J11") (pin "2") (pinfunction "2_2") (pintype "bidirectional"))
      (node (ref "J11") (pin "3") (pinfunction "3_3") (pintype "bidirectional"))
      (node (ref "J11") (pin "4") (pinfunction "4_4") (pintype "bidirectional"))
      (node (ref "J11") (pin "5") (pinfunction "5_5") (pintype "bidirectional"))
      (node (ref "J12") (pin "1") (pinfunction "1_1") (pintype "passive"))
    )
    (net (code "67") (name "Net-(J12-2)") (class "Default")
      (node (ref "J11") (pin "65") (pinfunction "65_65") (pintype "bidirectional"))
      (node (ref "J11") (pin "66") (pinfunction "66_66") (pintype "bidirectional"))
      (node (ref "J11") (pin "67") (pinfunction "67_67") (pintype "bidirectional"))
      (node (ref "J11") (pin "68") (pinfunction "68_68") (pintype "bidirectional"))
      (node (ref "J12") (pin "16") (pinfunction "2_16") (pintype "passive"))
    )
    (net (code "68") (name "Net-(J12-3)") (class "Default")
      (node (ref "J11") (pin "6") (pinfunction "6_6") (pintype "bidirectional"))
      (node (ref "J11") (pin "7") (pinfunction "7_7") (pintype "bidirectional"))
      (node (ref "J11") (pin "8") (pinfunction "8_8") (pintype "bidirectional"))
      (node (ref "J11") (pin "9") (pinfunction "9_9") (pintype "bidirectional"))
      (node (ref "J12") (pin "2") (pinfunction "3_2") (pintype "passive"))
    )
    (net (code "69") (name "Net-(J12-4)") (class "Default")
      (node (ref "J11") (pin "61") (pinfunction "61_61") (pintype "bidirectional"))
      (node (ref "J11") (pin "62") (pinfunction "62_62") (pintype "bidirectional"))
      (node (ref "J11") (pin "63") (pinfunction "63_63") (pintype "bidirectional"))
      (node (ref "J11") (pin "64") (pinfunction "64_64") (pintype "bidirectional"))
      (node (ref "J12") (pin "15") (pinfunction "4_15") (pintype "passive"))
    )
    (net (code "70") (name "Net-(J12-5)") (class "Default")
      (node (ref "J11") (pin "10") (pinfunction "10_10") (pintype "bidirectional"))
      (node (ref "J11") (pin "11") (pinfunction "11_11") (pintype "bidirectional"))
      (node (ref "J11") (pin "12") (pinfunction "12_12") (pintype "bidirectional"))
      (node (ref "J11") (pin "13") (pinfunction "13_13") (pintype "bidirectional"))
      (node (ref "J12") (pin "3") (pinfunction "5_3") (pintype "passive"))
    )
    (net (code "71") (name "Net-(J12-6)") (class "Default")
      (node (ref "J11") (pin "57") (pinfunction "57_57") (pintype "bidirectional"))
      (node (ref "J11") (pin "58") (pinfunction "58_58") (pintype "bidirectional"))
      (node (ref "J11") (pin "59") (pinfunction "59_59") (pintype "bidirectional"))
      (node (ref "J11") (pin "60") (pinfunction "60_60") (pintype "bidirectional"))
      (node (ref "J12") (pin "14") (pinfunction "6_14") (pintype "passive"))
    )
    (net (code "72") (name "Net-(J12-7)") (class "Default")
      (node (ref "J11") (pin "14") (pinfunction "14_14") (pintype "bidirectional"))
      (node (ref "J11") (pin "15") (pinfunction "15_15") (pintype "bidirectional"))
      (node (ref "J11") (pin "16") (pinfunction "16_16") (pintype "bidirectional"))
      (node (ref "J11") (pin "17") (pinfunction "17_17") (pintype "bidirectional"))
      (node (ref "J12") (pin "4") (pinfunction "7_4") (pintype "passive"))
    )
    (net (code "73") (name "Net-(J12-8)") (class "Default")
      (node (ref "J11") (pin "53") (pinfunction "53_53") (pintype "bidirectional"))
      (node (ref "J11") (pin "54") (pinfunction "54_54") (pintype "bidirectional"))
      (node (ref "J11") (pin "55") (pinfunction "55_55") (pintype "bidirectional"))
      (node (ref "J11") (pin "56") (pinfunction "56_56") (pintype "bidirectional"))
      (node (ref "J12") (pin "13") (pinfunction "8_13") (pintype "passive"))
    )
    (net (code "74") (name "Net-(J12-9)") (class "Default")
      (node (ref "J11") (pin "18") (pinfunction "18_18") (pintype "bidirectional"))
      (node (ref "J11") (pin "19") (pinfunction "19_19") (pintype "bidirectional"))
      (node (ref "J11") (pin "20") (pinfunction "20_20") (pintype "bidirectional"))
      (node (ref "J11") (pin "21") (pinfunction "21_21") (pintype "bidirectional"))
      (node (ref "J12") (pin "5") (pinfunction "9_5") (pintype "passive"))
    )
    (net (code "75") (name "Net-(J12-10)") (class "Default")
      (node (ref "J11") (pin "49") (pinfunction "49_49") (pintype "bidirectional"))
      (node (ref "J11") (pin "50") (pinfunction "50_50") (pintype "bidirectional"))
      (node (ref "J11") (pin "51") (pinfunction "51_51") (pintype "bidirectional"))
      (node (ref "J11") (pin "52") (pinfunction "52_52") (pintype "bidirectional"))
      (node (ref "J12") (pin "12") (pinfunction "10_12") (pintype "passive"))
    )
    (net (code "76") (name "Net-(J12-11)") (class "Default")
      (node (ref "J11") (pin "22") (pinfunction "22_22") (pintype "bidirectional"))
      (node (ref "J11") (pin "23") (pinfunction "23_23") (pintype "bidirectional"))
      (node (ref "J11") (pin "24") (pinfunction "24_24") (pintype "bidirectional"))
      (node (ref "J11") (pin "25") (pinfunction "25_25") (pintype "bidirectional"))
      (node (ref "J12") (pin "6") (pinfunction "11_6") (pintype "passive"))
    )
    (net (code "77") (name "Net-(J12-12)") (class "Default")
      (node (ref "J11") (pin "45") (pinfunction "45_45") (pintype "bidirectional"))
      (node (ref "J11") (pin "46") (pinfunction "46_46") (pintype "bidirectional"))
      (node (ref "J11") (pin "47") (pinfunction "47_47") (pintype "bidirectional"))
      (node (ref "J11") (pin "48") (pinfunction "48_48") (pintype "bidirectional"))
      (node (ref "J12") (pin "11") (pinfunction "12_11") (pintype "passive"))
    )
    (net (code "78") (name "Net-(J12-13)") (class "Default")
      (node (ref "J11") (pin "26") (pinfunction "26_26") (pintype "bidirectional"))
      (node (ref "J11") (pin "27") (pinfunction "27_27") (pintype "bidirectional"))
      (node (ref "J11") (pin "28") (pinfunction "28_28") (pintype "bidirectional"))
      (node (ref "J11") (pin "29") (pinfunction "29_29") (pintype "bidirectional"))
      (node (ref "J12") (pin "7") (pinfunction "13_7") (pintype "passive"))
    )
    (net (code "79") (name "Net-(J12-14)") (class "Default")
      (node (ref "J11") (pin "41") (pinfunction "41_41") (pintype "bidirectional"))
      (node (ref "J11") (pin "42") (pinfunction "42_42") (pintype "bidirectional"))
      (node (ref "J11") (pin "43") (pinfunction "43_43") (pintype "bidirectional"))
      (node (ref "J11") (pin "44") (pinfunction "44_44") (pintype "bidirectional"))
      (node (ref "J12") (pin "10") (pinfunction "14_10") (pintype "passive"))
    )
    (net (code "80") (name "Net-(J12-15)") (class "Default")
      (node (ref "J11") (pin "30") (pinfunction "30_30") (pintype "bidirectional"))
      (node (ref "J11") (pin "31") (pinfunction "31_31") (pintype "bidirectional"))
      (node (ref "J11") (pin "32") (pinfunction "32_32") (pintype "bidirectional"))
      (node (ref "J11") (pin "33") (pinfunction "33_33") (pintype "bidirectional"))
      (node (ref "J12") (pin "8") (pinfunction "15_8") (pintype "passive"))
    )
    (net (code "81") (name "Net-(J12-16)") (class "Default")
      (node (ref "J11") (pin "37") (pinfunction "37_37") (pintype "bidirectional"))
      (node (ref "J11") (pin "38") (pinfunction "38_38") (pintype "bidirectional"))
      (node (ref "J11") (pin "39") (pinfunction "39_39") (pintype "bidirectional"))
      (node (ref "J11") (pin "40") (pinfunction "40_40") (pintype "bidirectional"))
      (node (ref "J12") (pin "9") (pinfunction "16_9") (pintype "passive"))
    )
    (net (code "82") (name "unconnected-(J1-Pad34)") (class "Default")
      (node (ref "J1") (pin "34") (pinfunction "34_34") (pintype "bidirectional"))
    )
    (net (code "83") (name "unconnected-(J1-Pad35)") (class "Default")
      (node (ref "J1") (pin "35") (pinfunction "35_35") (pintype "bidirectional"))
    )
    (net (code "84") (name "unconnected-(J1-Pad36)") (class "Default")
      (node (ref "J1") (pin "36") (pinfunction "36_36") (pintype "bidirectional"))
    )
    (net (code "85") (name "unconnected-(J1-Pad69)") (class "Default")
      (node (ref "J1") (pin "69") (pinfunction "69_69") (pintype "bidirectional"))
    )
    (net (code "86") (name "unconnected-(J3-Pad34)") (class "Default")
      (node (ref "J3") (pin "34") (pinfunction "34_34") (pintype "bidirectional"))
    )
    (net (code "87") (name "unconnected-(J3-Pad35)") (class "Default")
      (node (ref "J3") (pin "35") (pinfunction "35_35") (pintype "bidirectional"))
    )
    (net (code "88") (name "unconnected-(J3-Pad36)") (class "Default")
      (node (ref "J3") (pin "36") (pinfunction "36_36") (pintype "bidirectional"))
    )
    (net (code "89") (name "unconnected-(J3-Pad69)") (class "Default")
      (node (ref "J3") (pin "69") (pinfunction "69_69") (pintype "bidirectional"))
    )
    (net (code "90") (name "unconnected-(J4-Pad34)") (class "Default")
      (node (ref "J4") (pin "34") (pinfunction "34_34") (pintype "bidirectional"))
    )
    (net (code "91") (name "unconnected-(J4-Pad35)") (class "Default")
      (node (ref "J4") (pin "35") (pinfunction "35_35") (pintype "bidirectional"))
    )
    (net (code "92") (name "unconnected-(J4-Pad36)") (class "Default")
      (node (ref "J4") (pin "36") (pinfunction "36_36") (pintype "bidirectional"))
    )
    (net (code "93") (name "unconnected-(J4-Pad70)") (class "Default")
      (node (ref "J4") (pin "70") (pinfunction "70_70") (pintype "bidirectional"))
    )
    (net (code "94") (name "unconnected-(J9-Pad34)") (class "Default")
      (node (ref "J9") (pin "34") (pinfunction "34_34") (pintype "bidirectional"))
    )
    (net (code "95") (name "unconnected-(J9-Pad35)") (class "Default")
      (node (ref "J9") (pin "35") (pinfunction "35_35") (pintype "bidirectional"))
    )
    (net (code "96") (name "unconnected-(J9-Pad36)") (class "Default")
      (node (ref "J9") (pin "36") (pinfunction "36_36") (pintype "bidirectional"))
    )
    (net (code "97") (name "unconnected-(J9-Pad69)") (class "Default")
      (node (ref "J9") (pin "69") (pinfunction "69_69") (pintype "bidirectional"))
    )
    (net (code "98") (name "unconnected-(J11-Pad34)") (class "Default")
      (node (ref "J11") (pin "34") (pinfunction "34_34") (pintype "bidirectional"))
    )
    (net (code "99") (name "unconnected-(J11-Pad35)") (class "Default")
      (node (ref "J11") (pin "35") (pinfunction "35_35") (pintype "bidirectional"))
    )
    (net (code "100") (name "unconnected-(J11-Pad36)") (class "Default")
      (node (ref "J11") (pin "36") (pinfunction "36_36") (pintype "bidirectional"))
    )
    (net (code "101") (name "unconnected-(J11-Pad69)") (class "Default")
      (node (ref "J11") (pin "69") (pinfunction "69_69") (pintype "bidirectional"))
    )
  )
)
